# TMS320F28335_DSP.net
KiCad netlist of a schematic drawn in Altium Designer
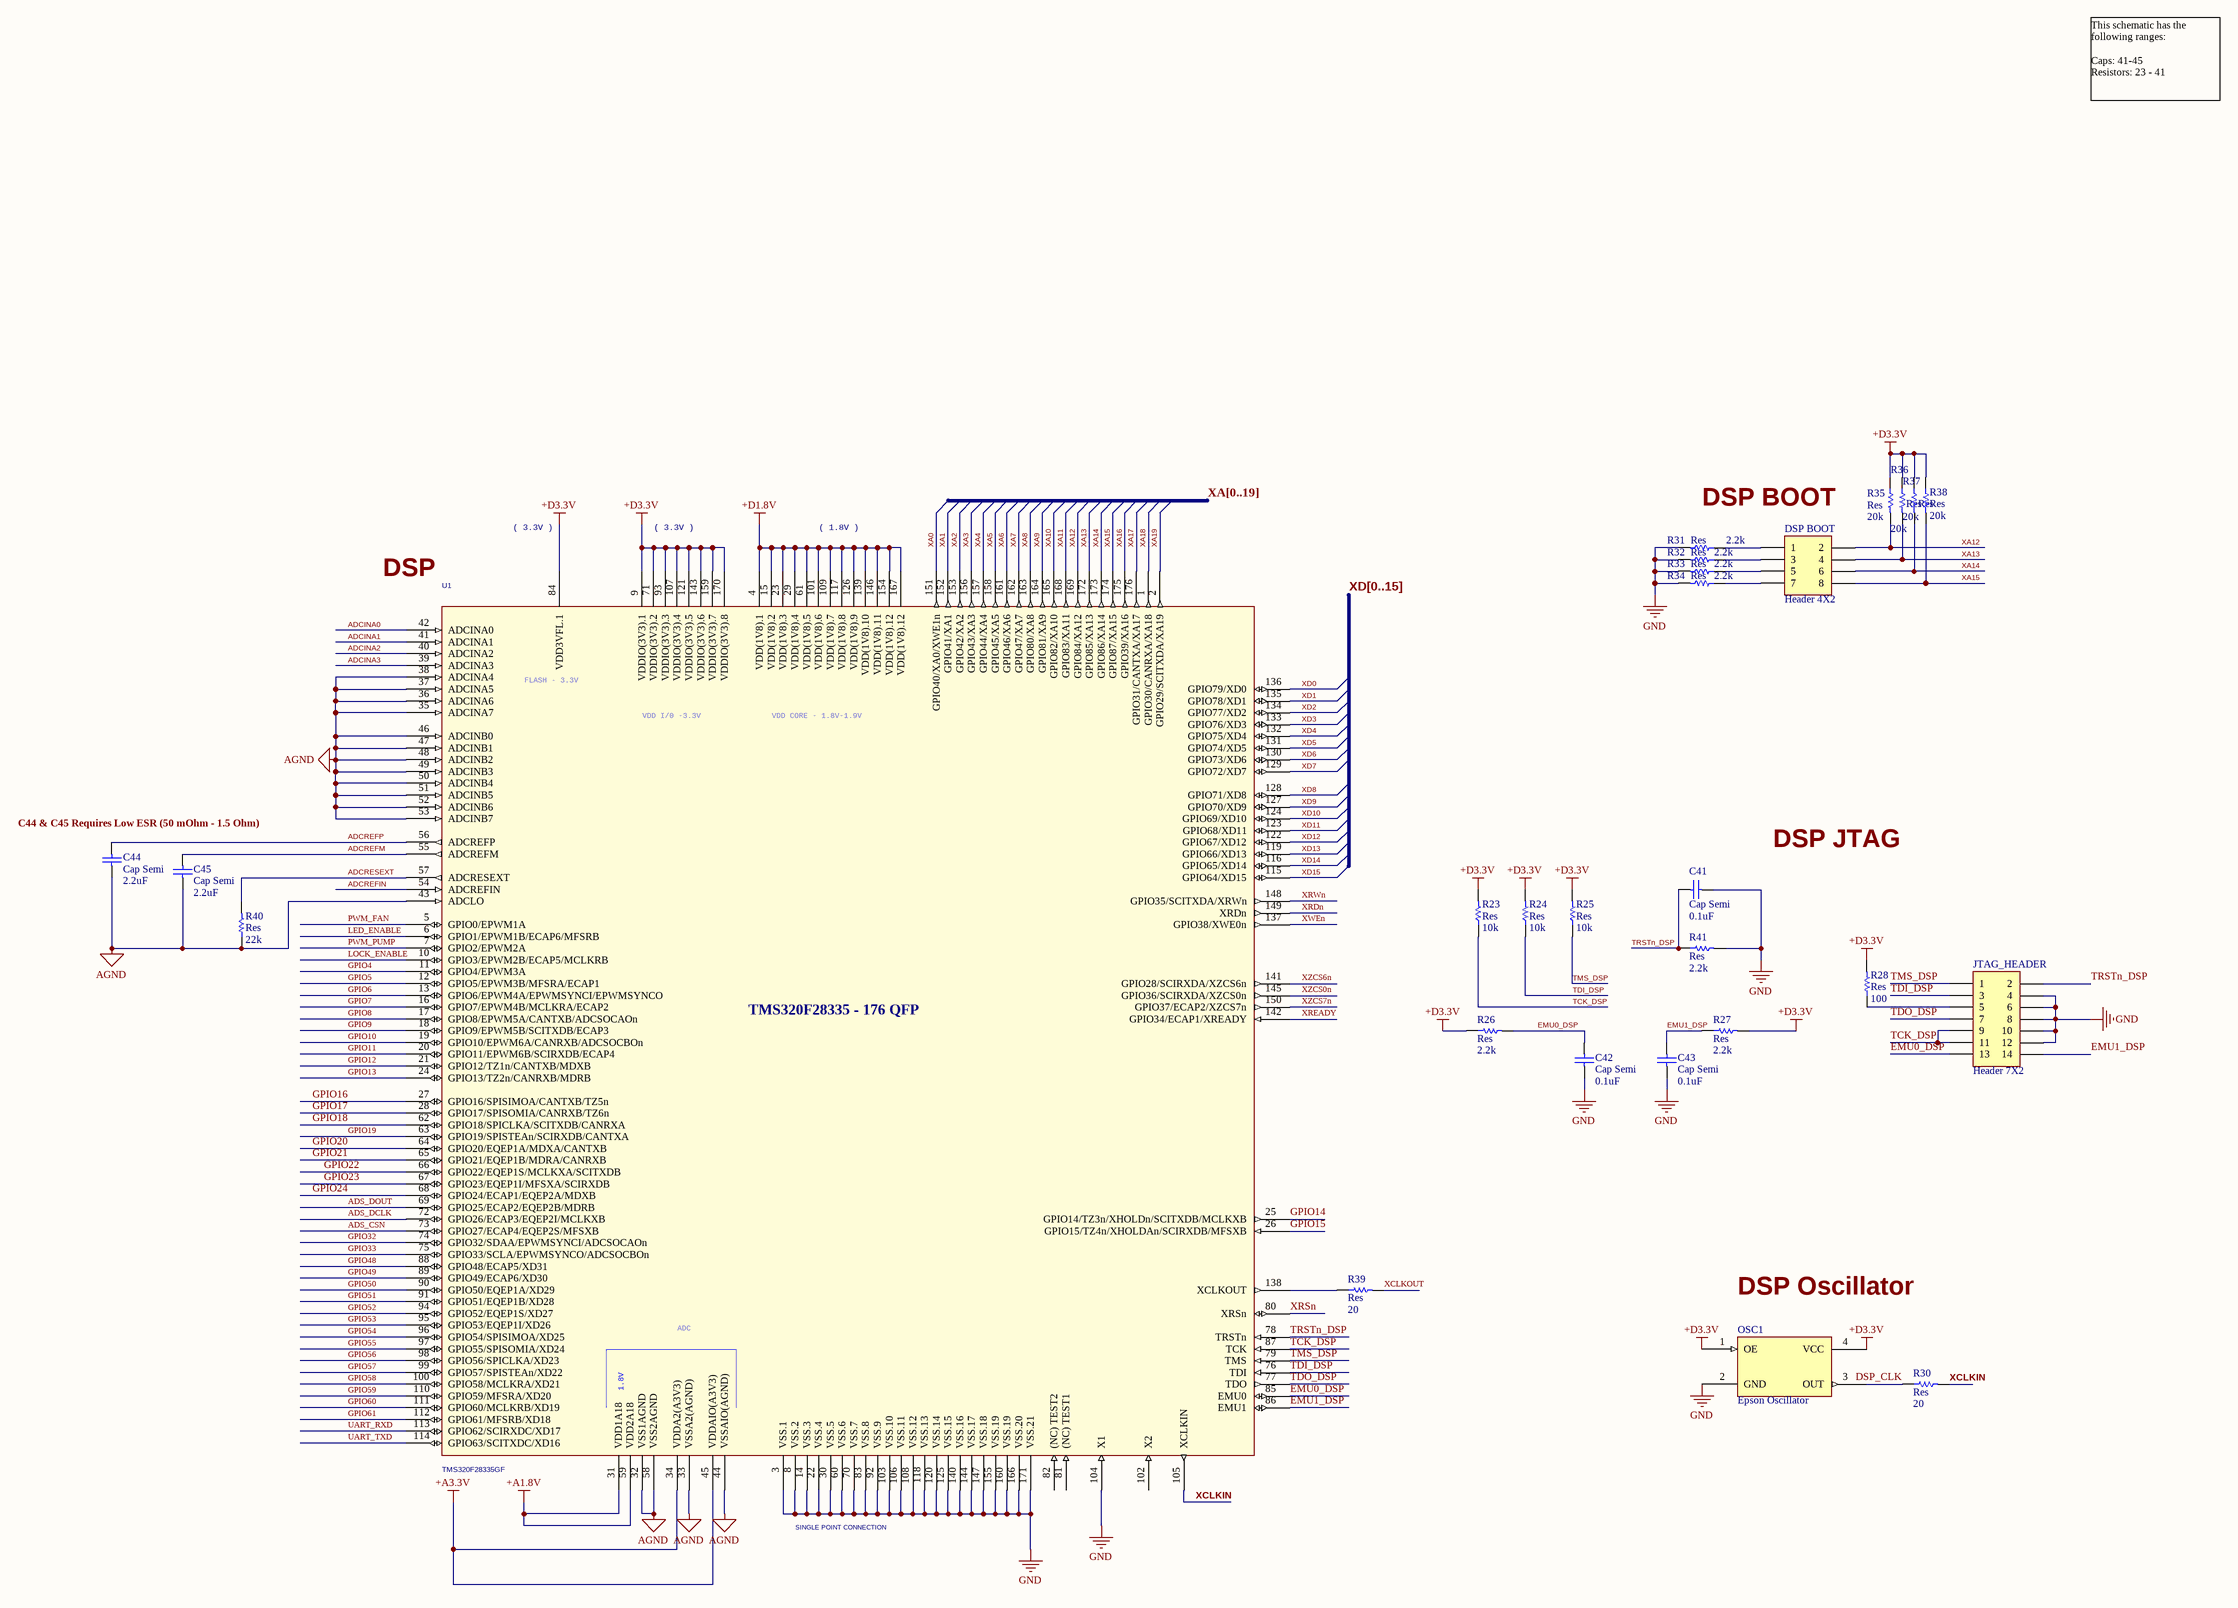
[diagram p0: TMS320F28335_DSP.SchDoc]

(export (version "E")
  (design (tool "Eeschema 10.0.6"))
  (components
    (comp (ref "C41")
      (value "Cap Semi")
      (footprint "0805")
      (description "Capacitor (Semiconductor SIM Model)")
      (fields (field (name "ALTIUM_VALUE") "0.1uF") (field (name "PUBLISHER") "Altium Limited"))
      (libsource (lib "Miscellaneous Devices") (part "Cap Semi"))
    )
    (comp (ref "C42")
      (value "Cap Semi")
      (footprint "0805")
      (description "Capacitor (Semiconductor SIM Model)")
      (fields (field (name "ALTIUM_VALUE") "0.1uF") (field (name "PUBLISHER") "Altium Limited"))
      (libsource (lib "Miscellaneous Devices") (part "Cap Semi"))
    )
    (comp (ref "C43")
      (value "Cap Semi")
      (footprint "0805")
      (description "Capacitor (Semiconductor SIM Model)")
      (fields (field (name "ALTIUM_VALUE") "0.1uF") (field (name "PUBLISHER") "Altium Limited"))
      (libsource (lib "Miscellaneous Devices") (part "Cap Semi"))
    )
    (comp (ref "C44")
      (value "Cap Semi")
      (footprint "0805")
      (description "Capacitor (Semiconductor SIM Model)")
      (fields (field (name "ALTIUM_VALUE") "2.2uF") (field (name "PUBLISHER") "Altium Limited"))
      (libsource (lib "Miscellaneous Devices") (part "Cap Semi"))
    )
    (comp (ref "C45")
      (value "Cap Semi")
      (footprint "0805")
      (description "Capacitor (Semiconductor SIM Model)")
      (fields (field (name "ALTIUM_VALUE") "2.2uF") (field (name "PUBLISHER") "Altium Limited"))
      (libsource (lib "Miscellaneous Devices") (part "Cap Semi"))
    )
    (comp (ref "DSP BOOT")
      (value "Header 4X2")
      (footprint "HDR2X4")
      (description "Header, 4-Pin, Dual row")
      (fields (field (name "PUBLISHER") "Altium Limited"))
      (libsource (lib "Miscellaneous Connectors") (part "Header 4X2"))
    )
    (comp (ref "JTAG_HEADER")
      (value "Header 7X2")
      (footprint "HDR2X7")
      (description "Header, 7-Pin, Dual row")
      (fields (field (name "PUBLISHER") "Altium Limited"))
      (libsource (lib "Miscellaneous Connectors") (part "Header 7X2"))
    )
    (comp (ref "OSC1")
      (value "Epson Oscillator")
      (footprint "Oscillator")
      (description "15Mhz Epson Clock")
      (libsource (lib "F28335_DSC_Breakout") (part "Oscillator"))
    )
    (comp (ref "R23")
      (value "Res")
      (footprint "0805")
      (description "Semiconductor Resistor")
      (fields (field (name "ALTIUM_VALUE") "10k") (field (name "PUBLISHER") "Altium Limited"))
      (libsource (lib "F28335_DSC_Breakout") (part "Res Semi"))
    )
    (comp (ref "R24")
      (value "Res")
      (footprint "0805")
      (description "Semiconductor Resistor")
      (fields (field (name "ALTIUM_VALUE") "10k") (field (name "PUBLISHER") "Altium Limited"))
      (libsource (lib "F28335_DSC_Breakout") (part "Res Semi"))
    )
    (comp (ref "R25")
      (value "Res")
      (footprint "0805")
      (description "Semiconductor Resistor")
      (fields (field (name "ALTIUM_VALUE") "10k") (field (name "PUBLISHER") "Altium Limited"))
      (libsource (lib "F28335_DSC_Breakout") (part "Res Semi"))
    )
    (comp (ref "R26")
      (value "Res")
      (footprint "0805")
      (description "Semiconductor Resistor")
      (fields (field (name "ALTIUM_VALUE") "2.2k") (field (name "PUBLISHER") "Altium Limited"))
      (libsource (lib "F28335_DSC_Breakout") (part "Res Semi"))
    )
    (comp (ref "R27")
      (value "Res")
      (footprint "0805")
      (description "Semiconductor Resistor")
      (fields (field (name "ALTIUM_VALUE") "2.2k") (field (name "PUBLISHER") "Altium Limited"))
      (libsource (lib "F28335_DSC_Breakout") (part "Res Semi"))
    )
    (comp (ref "R28")
      (value "Res")
      (footprint "0805")
      (description "Semiconductor Resistor")
      (fields (field (name "ALTIUM_VALUE") "100") (field (name "PUBLISHER") "Altium Limited"))
      (libsource (lib "F28335_DSC_Breakout") (part "Res Semi"))
    )
    (comp (ref "R30")
      (value "Res")
      (footprint "0805")
      (description "Semiconductor Resistor")
      (fields (field (name "ALTIUM_VALUE") "20") (field (name "PUBLISHER") "Altium Limited"))
      (libsource (lib "F28335_DSC_Breakout") (part "Res Semi"))
    )
    (comp (ref "R31")
      (value "Res")
      (footprint "0805")
      (description "Semiconductor Resistor")
      (fields (field (name "ALTIUM_VALUE") "2.2k") (field (name "PUBLISHER") "Altium Limited"))
      (libsource (lib "F28335_DSC_Breakout") (part "Res Semi"))
    )
    (comp (ref "R32")
      (value "Res")
      (footprint "0805")
      (description "Semiconductor Resistor")
      (fields (field (name "ALTIUM_VALUE") "2.2k") (field (name "PUBLISHER") "Altium Limited"))
      (libsource (lib "F28335_DSC_Breakout") (part "Res Semi"))
    )
    (comp (ref "R33")
      (value "Res")
      (footprint "0805")
      (description "Semiconductor Resistor")
      (fields (field (name "ALTIUM_VALUE") "2.2k") (field (name "PUBLISHER") "Altium Limited"))
      (libsource (lib "F28335_DSC_Breakout") (part "Res Semi"))
    )
    (comp (ref "R34")
      (value "Res")
      (footprint "0805")
      (description "Semiconductor Resistor")
      (fields (field (name "ALTIUM_VALUE") "2.2k") (field (name "PUBLISHER") "Altium Limited"))
      (libsource (lib "F28335_DSC_Breakout") (part "Res Semi"))
    )
    (comp (ref "R35")
      (value "Res")
      (footprint "0805")
      (description "Semiconductor Resistor")
      (fields (field (name "ALTIUM_VALUE") "20k") (field (name "PUBLISHER") "Altium Limited"))
      (libsource (lib "F28335_DSC_Breakout") (part "Res Semi"))
    )
    (comp (ref "R36")
      (value "Res")
      (footprint "0805")
      (description "Semiconductor Resistor")
      (fields (field (name "ALTIUM_VALUE") "20k") (field (name "PUBLISHER") "Altium Limited"))
      (libsource (lib "F28335_DSC_Breakout") (part "Res Semi"))
    )
    (comp (ref "R37")
      (value "Res")
      (footprint "0805")
      (description "Semiconductor Resistor")
      (fields (field (name "ALTIUM_VALUE") "20k") (field (name "PUBLISHER") "Altium Limited"))
      (libsource (lib "F28335_DSC_Breakout") (part "Res Semi"))
    )
    (comp (ref "R38")
      (value "Res")
      (footprint "0805")
      (description "Semiconductor Resistor")
      (fields (field (name "ALTIUM_VALUE") "20k") (field (name "PUBLISHER") "Altium Limited"))
      (libsource (lib "F28335_DSC_Breakout") (part "Res Semi"))
    )
    (comp (ref "R39")
      (value "Res")
      (footprint "0805")
      (description "Semiconductor Resistor")
      (fields (field (name "ALTIUM_VALUE") "20") (field (name "PUBLISHER") "Altium Limited"))
      (libsource (lib "F28335_DSC_Breakout") (part "Res Semi"))
    )
    (comp (ref "R40")
      (value "Res")
      (footprint "0805")
      (description "Semiconductor Resistor")
      (fields (field (name "ALTIUM_VALUE") "22k") (field (name "PUBLISHER") "Altium Limited"))
      (libsource (lib "F28335_DSC_Breakout") (part "Res Semi"))
    )
    (comp (ref "R41")
      (value "Res")
      (footprint "0805")
      (description "Semiconductor Resistor")
      (fields (field (name "ALTIUM_VALUE") "2.2k") (field (name "PUBLISHER") "Altium Limited"))
      (libsource (lib "F28335_DSC_Breakout") (part "Res Semi"))
    )
    (comp (ref "U1")
      (value "TMS320F28335GF")
      (footprint "QFP176")
      (description "Texas Instruments F28335")
      (libsource (lib "addl") (part "TMS320F283XXPGF_23"))
    )
  )
  (nets
    (net (code "1") (name "+A1.8V") (class "Default")
      (node (ref "U1") (pin "31") (pinfunction "VDD1A18_31") (pintype "power_in"))
      (node (ref "U1") (pin "59") (pinfunction "VDD2A18_59") (pintype "power_in"))
    )
    (net (code "2") (name "+A3.3V") (class "Default")
      (node (ref "U1") (pin "34") (pinfunction "VDDA2(A3V3)_34") (pintype "power_in"))
      (node (ref "U1") (pin "45") (pinfunction "VDDAIO(A3V3)_45") (pintype "power_in"))
    )
    (net (code "3") (name "+D1.8V") (class "Default")
      (node (ref "U1") (pin "101") (pinfunction "VDD(1V8).6_101") (pintype "power_in"))
      (node (ref "U1") (pin "109") (pinfunction "VDD(1V8).7_109") (pintype "power_in"))
      (node (ref "U1") (pin "117") (pinfunction "VDD(1V8).8_117") (pintype "power_in"))
      (node (ref "U1") (pin "126") (pinfunction "VDD(1V8).9_126") (pintype "power_in"))
      (node (ref "U1") (pin "139") (pinfunction "VDD(1V8).10_139") (pintype "power_in"))
      (node (ref "U1") (pin "146") (pinfunction "VDD(1V8).11_146") (pintype "power_in"))
      (node (ref "U1") (pin "15") (pinfunction "VDD(1V8).2_15") (pintype "power_in"))
      (node (ref "U1") (pin "154") (pinfunction "VDD(1V8).12_154") (pintype "power_in"))
      (node (ref "U1") (pin "167") (pinfunction "VDD(1V8).12_167") (pintype "power_in"))
      (node (ref "U1") (pin "23") (pinfunction "VDD(1V8).3_23") (pintype "power_in"))
      (node (ref "U1") (pin "29") (pinfunction "VDD(1V8).4_29") (pintype "power_in"))
      (node (ref "U1") (pin "4") (pinfunction "VDD(1V8).1_4") (pintype "power_in"))
      (node (ref "U1") (pin "61") (pinfunction "VDD(1V8).5_61") (pintype "power_in"))
    )
    (net (code "4") (name "+D3.3V") (class "Default")
      (node (ref "OSC1") (pin "1") (pinfunction "OE_1") (pintype "input"))
      (node (ref "OSC1") (pin "4") (pinfunction "VCC_4") (pintype "power_in"))
      (node (ref "R23") (pin "2") (pinfunction "2_2") (pintype "passive"))
      (node (ref "R24") (pin "2") (pinfunction "2_2") (pintype "passive"))
      (node (ref "R25") (pin "2") (pinfunction "2_2") (pintype "passive"))
      (node (ref "R26") (pin "1") (pinfunction "1_1") (pintype "passive"))
      (node (ref "R27") (pin "2") (pinfunction "2_2") (pintype "passive"))
      (node (ref "R28") (pin "2") (pinfunction "2_2") (pintype "passive"))
      (node (ref "R35") (pin "1") (pinfunction "1_1") (pintype "passive"))
      (node (ref "R36") (pin "1") (pinfunction "1_1") (pintype "passive"))
      (node (ref "R37") (pin "1") (pinfunction "1_1") (pintype "passive"))
      (node (ref "R38") (pin "1") (pinfunction "1_1") (pintype "passive"))
      (node (ref "U1") (pin "107") (pinfunction "VDDIO(3V3).4_107") (pintype "power_in"))
      (node (ref "U1") (pin "121") (pinfunction "VDDIO(3V3).5_121") (pintype "power_in"))
      (node (ref "U1") (pin "143") (pinfunction "VDDIO(3V3).6_143") (pintype "power_in"))
      (node (ref "U1") (pin "159") (pinfunction "VDDIO(3V3).7_159") (pintype "power_in"))
      (node (ref "U1") (pin "170") (pinfunction "VDDIO(3V3).8_170") (pintype "power_in"))
      (node (ref "U1") (pin "71") (pinfunction "VDDIO(3V3).2_71") (pintype "power_in"))
      (node (ref "U1") (pin "84") (pinfunction "VDD3VFL.1_84") (pintype "power_in"))
      (node (ref "U1") (pin "9") (pinfunction "VDDIO(3V3).1_9") (pintype "power_in"))
      (node (ref "U1") (pin "93") (pinfunction "VDDIO(3V3).3_93") (pintype "power_in"))
    )
    (net (code "5") (name "/ADCINA0") (class "Default")
      (node (ref "U1") (pin "42") (pinfunction "ADCINA0_42") (pintype "input"))
    )
    (net (code "6") (name "/ADCINA1") (class "Default")
      (node (ref "U1") (pin "41") (pinfunction "ADCINA1_41") (pintype "input"))
    )
    (net (code "7") (name "/ADCINA2") (class "Default")
      (node (ref "U1") (pin "40") (pinfunction "ADCINA2_40") (pintype "input"))
    )
    (net (code "8") (name "/ADCINA3") (class "Default")
      (node (ref "U1") (pin "39") (pinfunction "ADCINA3_39") (pintype "input"))
    )
    (net (code "9") (name "/ADCREFIN") (class "Default")
      (node (ref "U1") (pin "54") (pinfunction "ADCREFIN_54") (pintype "input"))
    )
    (net (code "10") (name "/ADCREFM") (class "Default")
      (node (ref "C45") (pin "1") (pinfunction "1_1") (pintype "passive"))
      (node (ref "U1") (pin "55") (pinfunction "ADCREFM_55") (pintype "output"))
    )
    (net (code "11") (name "/ADCREFP") (class "Default")
      (node (ref "C44") (pin "1") (pinfunction "1_1") (pintype "passive"))
      (node (ref "U1") (pin "56") (pinfunction "ADCREFP_56") (pintype "output"))
    )
    (net (code "12") (name "/ADCRESEXT") (class "Default")
      (node (ref "R40") (pin "2") (pinfunction "2_2") (pintype "passive"))
      (node (ref "U1") (pin "57") (pinfunction "ADCRESEXT_57") (pintype "output"))
    )
    (net (code "13") (name "/ADS_CSN") (class "Default")
      (node (ref "U1") (pin "73") (pinfunction "GPIO27/ECAP4/EQEP2S/MFSXB_73") (pintype "bidirectional"))
    )
    (net (code "14") (name "/ADS_DCLK") (class "Default")
      (node (ref "U1") (pin "72") (pinfunction "GPIO26/ECAP3/EQEP2I/MCLKXB_72") (pintype "bidirectional"))
    )
    (net (code "15") (name "/ADS_DOUT") (class "Default")
      (node (ref "U1") (pin "69") (pinfunction "GPIO25/ECAP2/EQEP2B/MDRB_69") (pintype "bidirectional"))
    )
    (net (code "17") (name "/EMU0_DSP") (class "Default")
      (node (ref "C42") (pin "2") (pinfunction "2_2") (pintype "passive"))
      (node (ref "JTAG_HEADER") (pin "13") (pinfunction "13_13") (pintype "passive"))
      (node (ref "R26") (pin "2") (pinfunction "2_2") (pintype "passive"))
      (node (ref "U1") (pin "85") (pinfunction "EMU0_85") (pintype "bidirectional"))
    )
    (net (code "18") (name "/EMU1_DSP") (class "Default")
      (node (ref "C43") (pin "2") (pinfunction "2_2") (pintype "passive"))
      (node (ref "JTAG_HEADER") (pin "14") (pinfunction "14_14") (pintype "passive"))
      (node (ref "R27") (pin "1") (pinfunction "1_1") (pintype "passive"))
      (node (ref "U1") (pin "86") (pinfunction "EMU1_86") (pintype "bidirectional"))
    )
    (net (code "19") (name "/GPIO4") (class "Default")
      (node (ref "U1") (pin "11") (pinfunction "GPIO4/EPWM3A_11") (pintype "bidirectional"))
    )
    (net (code "20") (name "/GPIO5") (class "Default")
      (node (ref "U1") (pin "12") (pinfunction "GPIO5/EPWM3B/MFSRA/ECAP1_12") (pintype "bidirectional"))
    )
    (net (code "21") (name "/GPIO6") (class "Default")
      (node (ref "U1") (pin "13") (pinfunction "GPIO6/EPWM4A/EPWMSYNCI/EPWMSYNCO_13") (pintype "bidirectional"))
    )
    (net (code "22") (name "/GPIO7") (class "Default")
      (node (ref "U1") (pin "16") (pinfunction "GPIO7/EPWM4B/MCLKRA/ECAP2_16") (pintype "bidirectional"))
    )
    (net (code "23") (name "/GPIO8") (class "Default")
      (node (ref "U1") (pin "17") (pinfunction "GPIO8/EPWM5A/CANTXB/ADCSOCAOn_17") (pintype "bidirectional"))
    )
    (net (code "24") (name "/GPIO9") (class "Default")
      (node (ref "U1") (pin "18") (pinfunction "GPIO9/EPWM5B/SCITXDB/ECAP3_18") (pintype "bidirectional"))
    )
    (net (code "25") (name "/GPIO10") (class "Default")
      (node (ref "U1") (pin "19") (pinfunction "GPIO10/EPWM6A/CANRXB/ADCSOCBOn_19") (pintype "bidirectional"))
    )
    (net (code "26") (name "/GPIO11") (class "Default")
      (node (ref "U1") (pin "20") (pinfunction "GPIO11/EPWM6B/SCIRXDB/ECAP4_20") (pintype "bidirectional"))
    )
    (net (code "27") (name "/GPIO12") (class "Default")
      (node (ref "U1") (pin "21") (pinfunction "GPIO12/TZ1n/CANTXB/MDXB_21") (pintype "bidirectional"))
    )
    (net (code "28") (name "/GPIO13") (class "Default")
      (node (ref "U1") (pin "24") (pinfunction "GPIO13/TZ2n/CANRXB/MDRB_24") (pintype "bidirectional"))
    )
    (net (code "29") (name "/GPIO14") (class "Default")
      (node (ref "U1") (pin "25") (pinfunction "GPIO14/TZ3n/XHOLDn/SCITXDB/MCLKXB_25") (pintype "output"))
    )
    (net (code "30") (name "/GPIO15") (class "Default")
      (node (ref "U1") (pin "26") (pinfunction "GPIO15/TZ4n/XHOLDAn/SCIRXDB/MFSXB_26") (pintype "input"))
    )
    (net (code "31") (name "/GPIO16") (class "Default")
      (node (ref "U1") (pin "27") (pinfunction "GPIO16/SPISIMOA/CANTXB/TZ5n_27") (pintype "bidirectional"))
    )
    (net (code "32") (name "/GPIO17") (class "Default")
      (node (ref "U1") (pin "28") (pinfunction "GPIO17/SPISOMIA/CANRXB/TZ6n_28") (pintype "bidirectional"))
    )
    (net (code "33") (name "/GPIO18") (class "Default")
      (node (ref "U1") (pin "62") (pinfunction "GPIO18/SPICLKA/SCITXDB/CANRXA_62") (pintype "bidirectional"))
    )
    (net (code "34") (name "/GPIO19") (class "Default")
      (node (ref "U1") (pin "63") (pinfunction "GPIO19/SPISTEAn/SCIRXDB/CANTXA_63") (pintype "bidirectional"))
    )
    (net (code "35") (name "/GPIO20") (class "Default")
      (node (ref "U1") (pin "64") (pinfunction "GPIO20/EQEP1A/MDXA/CANTXB_64") (pintype "bidirectional"))
    )
    (net (code "36") (name "/GPIO21") (class "Default")
      (node (ref "U1") (pin "65") (pinfunction "GPIO21/EQEP1B/MDRA/CANRXB_65") (pintype "bidirectional"))
    )
    (net (code "37") (name "/GPIO22") (class "Default")
      (node (ref "U1") (pin "66") (pinfunction "GPIO22/EQEP1S/MCLKXA/SCITXDB_66") (pintype "bidirectional"))
    )
    (net (code "38") (name "/GPIO23") (class "Default")
      (node (ref "U1") (pin "67") (pinfunction "GPIO23/EQEP1I/MFSXA/SCIRXDB_67") (pintype "bidirectional"))
    )
    (net (code "39") (name "/GPIO24") (class "Default")
      (node (ref "U1") (pin "68") (pinfunction "GPIO24/ECAP1/EQEP2A/MDXB_68") (pintype "bidirectional"))
    )
    (net (code "40") (name "/GPIO32") (class "Default")
      (node (ref "U1") (pin "74") (pinfunction "GPIO32/SDAA/EPWMSYNCI/ADCSOCAOn_74") (pintype "bidirectional"))
    )
    (net (code "41") (name "/GPIO33") (class "Default")
      (node (ref "U1") (pin "75") (pinfunction "GPIO33/SCLA/EPWMSYNCO/ADCSOCBOn_75") (pintype "bidirectional"))
    )
    (net (code "42") (name "/GPIO48") (class "Default")
      (node (ref "U1") (pin "88") (pinfunction "GPIO48/ECAP5/XD31_88") (pintype "bidirectional"))
    )
    (net (code "43") (name "/GPIO49") (class "Default")
      (node (ref "U1") (pin "89") (pinfunction "GPIO49/ECAP6/XD30_89") (pintype "bidirectional"))
    )
    (net (code "44") (name "/GPIO50") (class "Default")
      (node (ref "U1") (pin "90") (pinfunction "GPIO50/EQEP1A/XD29_90") (pintype "bidirectional"))
    )
    (net (code "45") (name "/GPIO51") (class "Default")
      (node (ref "U1") (pin "91") (pinfunction "GPIO51/EQEP1B/XD28_91") (pintype "bidirectional"))
    )
    (net (code "46") (name "/GPIO52") (class "Default")
      (node (ref "U1") (pin "94") (pinfunction "GPIO52/EQEP1S/XD27_94") (pintype "bidirectional"))
    )
    (net (code "47") (name "/GPIO53") (class "Default")
      (node (ref "U1") (pin "95") (pinfunction "GPIO53/EQEP1I/XD26_95") (pintype "bidirectional"))
    )
    (net (code "48") (name "/GPIO54") (class "Default")
      (node (ref "U1") (pin "96") (pinfunction "GPIO54/SPISIMOA/XD25_96") (pintype "bidirectional"))
    )
    (net (code "49") (name "/GPIO55") (class "Default")
      (node (ref "U1") (pin "97") (pinfunction "GPIO55/SPISOMIA/XD24_97") (pintype "bidirectional"))
    )
    (net (code "50") (name "/GPIO56") (class "Default")
      (node (ref "U1") (pin "98") (pinfunction "GPIO56/SPICLKA/XD23_98") (pintype "bidirectional"))
    )
    (net (code "51") (name "/GPIO57") (class "Default")
      (node (ref "U1") (pin "99") (pinfunction "GPIO57/SPISTEAn/XD22_99") (pintype "bidirectional"))
    )
    (net (code "52") (name "/GPIO58") (class "Default")
      (node (ref "U1") (pin "100") (pinfunction "GPIO58/MCLKRA/XD21_100") (pintype "bidirectional"))
    )
    (net (code "53") (name "/GPIO59") (class "Default")
      (node (ref "U1") (pin "110") (pinfunction "GPIO59/MFSRA/XD20_110") (pintype "bidirectional"))
    )
    (net (code "54") (name "/GPIO60") (class "Default")
      (node (ref "U1") (pin "111") (pinfunction "GPIO60/MCLKRB/XD19_111") (pintype "bidirectional"))
    )
    (net (code "55") (name "/GPIO61") (class "Default")
      (node (ref "U1") (pin "112") (pinfunction "GPIO61/MFSRB/XD18_112") (pintype "bidirectional"))
    )
    (net (code "56") (name "/LED_ENABLE") (class "Default")
      (node (ref "U1") (pin "6") (pinfunction "GPIO1/EPWM1B/ECAP6/MFSRB_6") (pintype "bidirectional"))
    )
    (net (code "57") (name "/LOCK_ENABLE") (class "Default")
      (node (ref "U1") (pin "10") (pinfunction "GPIO3/EPWM2B/ECAP5/MCLKRB_10") (pintype "bidirectional"))
    )
    (net (code "58") (name "/PWM_FAN") (class "Default")
      (node (ref "U1") (pin "5") (pinfunction "GPIO0/EPWM1A_5") (pintype "bidirectional"))
    )
    (net (code "59") (name "/PWM_PUMP") (class "Default")
      (node (ref "U1") (pin "7") (pinfunction "GPIO2/EPWM2A_7") (pintype "bidirectional"))
    )
    (net (code "60") (name "/TCK_DSP") (class "Default")
      (node (ref "JTAG_HEADER") (pin "11") (pinfunction "11_11") (pintype "passive"))
      (node (ref "JTAG_HEADER") (pin "9") (pinfunction "9_9") (pintype "passive"))
      (node (ref "R23") (pin "1") (pinfunction "1_1") (pintype "passive"))
      (node (ref "U1") (pin "87") (pinfunction "TCK_87") (pintype "input"))
    )
    (net (code "61") (name "/TDI_DSP") (class "Default")
      (node (ref "JTAG_HEADER") (pin "3") (pinfunction "3_3") (pintype "passive"))
      (node (ref "R24") (pin "1") (pinfunction "1_1") (pintype "passive"))
      (node (ref "U1") (pin "76") (pinfunction "TDI_76") (pintype "input"))
    )
    (net (code "62") (name "/TDO_DSP") (class "Default")
      (node (ref "JTAG_HEADER") (pin "7") (pinfunction "7_7") (pintype "passive"))
      (node (ref "U1") (pin "77") (pinfunction "TDO_77") (pintype "output"))
    )
    (net (code "63") (name "/TMS_DSP") (class "Default")
      (node (ref "JTAG_HEADER") (pin "1") (pinfunction "1_1") (pintype "passive"))
      (node (ref "R25") (pin "1") (pinfunction "1_1") (pintype "passive"))
      (node (ref "U1") (pin "79") (pinfunction "TMS_79") (pintype "input"))
    )
    (net (code "64") (name "/TRSTn_DSP") (class "Default")
      (node (ref "C41") (pin "2") (pinfunction "2_2") (pintype "passive"))
      (node (ref "JTAG_HEADER") (pin "2") (pinfunction "2_2") (pintype "passive"))
      (node (ref "R41") (pin "1") (pinfunction "1_1") (pintype "passive"))
      (node (ref "U1") (pin "78") (pinfunction "TRSTn_78") (pintype "input"))
    )
    (net (code "65") (name "/UART_RXD") (class "Default")
      (node (ref "U1") (pin "113") (pinfunction "GPIO62/SCIRXDC/XD17_113") (pintype "bidirectional"))
    )
    (net (code "66") (name "/UART_TXD") (class "Default")
      (node (ref "U1") (pin "114") (pinfunction "GPIO63/SCITXDC/XD16_114") (pintype "bidirectional"))
    )
    (net (code "67") (name "/XA0") (class "Default")
      (node (ref "U1") (pin "151") (pinfunction "GPIO40/XA0/XWE1n_151") (pintype "output"))
    )
    (net (code "68") (name "/XA1") (class "Default")
      (node (ref "U1") (pin "152") (pinfunction "GPIO41/XA1_152") (pintype "output"))
    )
    (net (code "69") (name "/XA2") (class "Default")
      (node (ref "U1") (pin "153") (pinfunction "GPIO42/XA2_153") (pintype "output"))
    )
    (net (code "70") (name "/XA3") (class "Default")
      (node (ref "U1") (pin "156") (pinfunction "GPIO43/XA3_156") (pintype "output"))
    )
    (net (code "71") (name "/XA4") (class "Default")
      (node (ref "U1") (pin "157") (pinfunction "GPIO44/XA4_157") (pintype "output"))
    )
    (net (code "72") (name "/XA5") (class "Default")
      (node (ref "U1") (pin "158") (pinfunction "GPIO45/XA5_158") (pintype "output"))
    )
    (net (code "73") (name "/XA6") (class "Default")
      (node (ref "U1") (pin "161") (pinfunction "GPIO46/XA6_161") (pintype "output"))
    )
    (net (code "74") (name "/XA7") (class "Default")
      (node (ref "U1") (pin "162") (pinfunction "GPIO47/XA7_162") (pintype "output"))
    )
    (net (code "75") (name "/XA8") (class "Default")
      (node (ref "U1") (pin "163") (pinfunction "GPIO80/XA8_163") (pintype "output"))
    )
    (net (code "76") (name "/XA9") (class "Default")
      (node (ref "U1") (pin "164") (pinfunction "GPIO81/XA9_164") (pintype "output"))
    )
    (net (code "77") (name "/XA10") (class "Default")
      (node (ref "U1") (pin "165") (pinfunction "GPIO82/XA10_165") (pintype "output"))
    )
    (net (code "78") (name "/XA11") (class "Default")
      (node (ref "U1") (pin "168") (pinfunction "GPIO83/XA11_168") (pintype "output"))
    )
    (net (code "79") (name "/XA12") (class "Default")
      (node (ref "DSP BOOT") (pin "2") (pinfunction "2_2") (pintype "passive"))
      (node (ref "R35") (pin "2") (pinfunction "2_2") (pintype "passive"))
      (node (ref "U1") (pin "169") (pinfunction "GPIO84/XA12_169") (pintype "output"))
    )
    (net (code "80") (name "/XA13") (class "Default")
      (node (ref "DSP BOOT") (pin "4") (pinfunction "4_4") (pintype "passive"))
      (node (ref "R36") (pin "2") (pinfunction "2_2") (pintype "passive"))
      (node (ref "U1") (pin "172") (pinfunction "GPIO85/XA13_172") (pintype "output"))
    )
    (net (code "81") (name "/XA14") (class "Default")
      (node (ref "DSP BOOT") (pin "6") (pinfunction "6_6") (pintype "passive"))
      (node (ref "R37") (pin "2") (pinfunction "2_2") (pintype "passive"))
      (node (ref "U1") (pin "173") (pinfunction "GPIO86/XA14_173") (pintype "output"))
    )
    (net (code "82") (name "/XA15") (class "Default")
      (node (ref "DSP BOOT") (pin "8") (pinfunction "8_8") (pintype "passive"))
      (node (ref "R38") (pin "2") (pinfunction "2_2") (pintype "passive"))
      (node (ref "U1") (pin "174") (pinfunction "GPIO87/XA15_174") (pintype "output"))
    )
    (net (code "83") (name "/XA16") (class "Default")
      (node (ref "U1") (pin "175") (pinfunction "GPIO39/XA16_175") (pintype "output"))
    )
    (net (code "84") (name "/XA17") (class "Default")
      (node (ref "U1") (pin "176") (pinfunction "GPIO31/CANTXA/XA17_176") (pintype "output"))
    )
    (net (code "85") (name "/XA18") (class "Default")
      (node (ref "U1") (pin "1") (pinfunction "GPIO30/CANRXA/XA18_1") (pintype "output"))
    )
    (net (code "86") (name "/XA19") (class "Default")
      (node (ref "U1") (pin "2") (pinfunction "GPIO29/SCITXDA/XA19_2") (pintype "output"))
    )
    (net (code "88") (name "/XCLKIN") (class "Default")
      (node (ref "R30") (pin "2") (pinfunction "2_2") (pintype "passive"))
      (node (ref "U1") (pin "105") (pinfunction "XCLKIN_105") (pintype "output"))
    )
    (net (code "89") (name "/XCLKOUT") (class "Default")
      (node (ref "R39") (pin "2") (pinfunction "2_2") (pintype "passive"))
    )
    (net (code "90") (name "/XD0") (class "Default")
      (node (ref "U1") (pin "136") (pinfunction "GPIO79/XD0_136") (pintype "bidirectional"))
    )
    (net (code "91") (name "/XD1") (class "Default")
      (node (ref "U1") (pin "135") (pinfunction "GPIO78/XD1_135") (pintype "bidirectional"))
    )
    (net (code "92") (name "/XD2") (class "Default")
      (node (ref "U1") (pin "134") (pinfunction "GPIO77/XD2_134") (pintype "bidirectional"))
    )
    (net (code "93") (name "/XD3") (class "Default")
      (node (ref "U1") (pin "133") (pinfunction "GPIO76/XD3_133") (pintype "bidirectional"))
    )
    (net (code "94") (name "/XD4") (class "Default")
      (node (ref "U1") (pin "132") (pinfunction "GPIO75/XD4_132") (pintype "bidirectional"))
    )
    (net (code "95") (name "/XD5") (class "Default")
      (node (ref "U1") (pin "131") (pinfunction "GPIO74/XD5_131") (pintype "bidirectional"))
    )
    (net (code "96") (name "/XD6") (class "Default")
      (node (ref "U1") (pin "130") (pinfunction "GPIO73/XD6_130") (pintype "bidirectional"))
    )
    (net (code "97") (name "/XD7") (class "Default")
      (node (ref "U1") (pin "129") (pinfunction "GPIO72/XD7_129") (pintype "bidirectional"))
    )
    (net (code "98") (name "/XD8") (class "Default")
      (node (ref "U1") (pin "128") (pinfunction "GPIO71/XD8_128") (pintype "bidirectional"))
    )
    (net (code "99") (name "/XD9") (class "Default")
      (node (ref "U1") (pin "127") (pinfunction "GPIO70/XD9_127") (pintype "bidirectional"))
    )
    (net (code "100") (name "/XD10") (class "Default")
      (node (ref "U1") (pin "124") (pinfunction "GPIO69/XD10_124") (pintype "bidirectional"))
    )
    (net (code "101") (name "/XD11") (class "Default")
      (node (ref "U1") (pin "123") (pinfunction "GPIO68/XD11_123") (pintype "bidirectional"))
    )
    (net (code "102") (name "/XD12") (class "Default")
      (node (ref "U1") (pin "122") (pinfunction "GPIO67/XD12_122") (pintype "bidirectional"))
    )
    (net (code "103") (name "/XD13") (class "Default")
      (node (ref "U1") (pin "119") (pinfunction "GPIO66/XD13_119") (pintype "bidirectional"))
    )
    (net (code "104") (name "/XD14") (class "Default")
      (node (ref "U1") (pin "116") (pinfunction "GPIO65/XD14_116") (pintype "bidirectional"))
    )
    (net (code "105") (name "/XD15") (class "Default")
      (node (ref "U1") (pin "115") (pinfunction "GPIO64/XD15_115") (pintype "bidirectional"))
    )
    (net (code "107") (name "/XRDn") (class "Default")
      (node (ref "U1") (pin "149") (pinfunction "XRDn_149") (pintype "output"))
    )
    (net (code "108") (name "/XREADY") (class "Default")
      (node (ref "U1") (pin "142") (pinfunction "GPIO34/ECAP1/XREADY_142") (pintype "input"))
    )
    (net (code "109") (name "/XRSn") (class "Default")
      (node (ref "U1") (pin "80") (pinfunction "XRSn_80") (pintype "bidirectional"))
    )
    (net (code "110") (name "/XRWn") (class "Default")
      (node (ref "U1") (pin "148") (pinfunction "GPIO35/SCITXDA/XRWn_148") (pintype "output"))
    )
    (net (code "111") (name "/XWEn") (class "Default")
      (node (ref "U1") (pin "137") (pinfunction "GPIO38/XWE0n_137") (pintype "output"))
    )
    (net (code "112") (name "/XZCS0n") (class "Default")
      (node (ref "U1") (pin "145") (pinfunction "GPIO36/SCIRXDA/XZCS0n_145") (pintype "output"))
    )
    (net (code "113") (name "/XZCS6n") (class "Default")
      (node (ref "U1") (pin "141") (pinfunction "GPIO28/SCIRXDA/XZCS6n_141") (pintype "output"))
    )
    (net (code "114") (name "/XZCS7n") (class "Default")
      (node (ref "U1") (pin "150") (pinfunction "GPIO37/ECAP2/XZCS7n_150") (pintype "output"))
    )
    (net (code "115") (name "AGND") (class "Default")
      (node (ref "C44") (pin "2") (pinfunction "2_2") (pintype "passive"))
      (node (ref "C45") (pin "2") (pinfunction "2_2") (pintype "passive"))
      (node (ref "R40") (pin "1") (pinfunction "1_1") (pintype "passive"))
      (node (ref "U1") (pin "32") (pinfunction "VSS1AGND_32") (pintype "power_in"))
      (node (ref "U1") (pin "33") (pinfunction "VSSA2(AGND)_33") (pintype "power_in"))
      (node (ref "U1") (pin "35") (pinfunction "ADCINA7_35") (pintype "input"))
      (node (ref "U1") (pin "36") (pinfunction "ADCINA6_36") (pintype "input"))
      (node (ref "U1") (pin "37") (pinfunction "ADCINA5_37") (pintype "input"))
      (node (ref "U1") (pin "38") (pinfunction "ADCINA4_38") (pintype "input"))
      (node (ref "U1") (pin "43") (pinfunction "ADCLO_43") (pintype "input"))
      (node (ref "U1") (pin "44") (pinfunction "VSSAIO(AGND)_44") (pintype "power_in"))
      (node (ref "U1") (pin "46") (pinfunction "ADCINB0_46") (pintype "input"))
      (node (ref "U1") (pin "47") (pinfunction "ADCINB1_47") (pintype "input"))
      (node (ref "U1") (pin "48") (pinfunction "ADCINB2_48") (pintype "input"))
      (node (ref "U1") (pin "49") (pinfunction "ADCINB3_49") (pintype "input"))
      (node (ref "U1") (pin "50") (pinfunction "ADCINB4_50") (pintype "input"))
      (node (ref "U1") (pin "51") (pinfunction "ADCINB5_51") (pintype "input"))
      (node (ref "U1") (pin "52") (pinfunction "ADCINB6_52") (pintype "input"))
      (node (ref "U1") (pin "53") (pinfunction "ADCINB7_53") (pintype "input"))
      (node (ref "U1") (pin "58") (pinfunction "VSS2AGND_58") (pintype "power_in"))
    )
    (net (code "116") (name "GND") (class "Default")
      (node (ref "C41") (pin "1") (pinfunction "1_1") (pintype "passive"))
      (node (ref "C42") (pin "1") (pinfunction "1_1") (pintype "passive"))
      (node (ref "C43") (pin "1") (pinfunction "1_1") (pintype "passive"))
      (node (ref "JTAG_HEADER") (pin "10") (pinfunction "10_10") (pintype "passive"))
      (node (ref "JTAG_HEADER") (pin "12") (pinfunction "12_12") (pintype "passive"))
      (node (ref "JTAG_HEADER") (pin "4") (pinfunction "4_4") (pintype "passive"))
      (node (ref "JTAG_HEADER") (pin "6") (pinfunction "6_6") (pintype "passive"))
      (node (ref "JTAG_HEADER") (pin "8") (pinfunction "8_8") (pintype "passive"))
      (node (ref "OSC1") (pin "2") (pinfunction "GND_2") (pintype "power_in"))
      (node (ref "R31") (pin "2") (pinfunction "2_2") (pintype "passive"))
      (node (ref "R32") (pin "2") (pinfunction "2_2") (pintype "passive"))
      (node (ref "R33") (pin "2") (pinfunction "2_2") (pintype "passive"))
      (node (ref "R34") (pin "2") (pinfunction "2_2") (pintype "passive"))
      (node (ref "R41") (pin "2") (pinfunction "2_2") (pintype "passive"))
      (node (ref "U1") (pin "103") (pinfunction "VSS.10_103") (pintype "power_in"))
      (node (ref "U1") (pin "104") (pinfunction "X1_104") (pintype "input"))
      (node (ref "U1") (pin "106") (pinfunction "VSS.11_106") (pintype "power_in"))
      (node (ref "U1") (pin "108") (pinfunction "VSS.12_108") (pintype "power_in"))
      (node (ref "U1") (pin "118") (pinfunction "VSS.13_118") (pintype "power_in"))
      (node (ref "U1") (pin "120") (pinfunction "VSS.14_120") (pintype "power_in"))
      (node (ref "U1") (pin "125") (pinfunction "VSS.15_125") (pintype "power_in"))
      (node (ref "U1") (pin "14") (pinfunction "VSS.3_14") (pintype "power_in"))
      (node (ref "U1") (pin "140") (pinfunction "VSS.16_140") (pintype "power_in"))
      (node (ref "U1") (pin "144") (pinfunction "VSS.17_144") (pintype "power_in"))
      (node (ref "U1") (pin "147") (pinfunction "VSS.18_147") (pintype "power_in"))
      (node (ref "U1") (pin "155") (pinfunction "VSS.19_155") (pintype "power_in"))
      (node (ref "U1") (pin "160") (pinfunction "VSS.19_160") (pintype "power_in"))
      (node (ref "U1") (pin "166") (pinfunction "VSS.20_166") (pintype "power_in"))
      (node (ref "U1") (pin "171") (pinfunction "VSS.21_171") (pintype "power_in"))
      (node (ref "U1") (pin "22") (pinfunction "VSS.4_22") (pintype "power_in"))
      (node (ref "U1") (pin "3") (pinfunction "VSS.1_3") (pintype "power_in"))
      (node (ref "U1") (pin "30") (pinfunction "VSS.5_30") (pintype "power_in"))
      (node (ref "U1") (pin "60") (pinfunction "VSS.6_60") (pintype "power_in"))
      (node (ref "U1") (pin "70") (pinfunction "VSS.7_70") (pintype "power_in"))
      (node (ref "U1") (pin "8") (pinfunction "VSS.2_8") (pintype "power_in"))
      (node (ref "U1") (pin "83") (pinfunction "VSS.8_83") (pintype "power_in"))
      (node (ref "U1") (pin "92") (pinfunction "VSS.9_92") (pintype "power_in"))
    )
    (net (code "117") (name "Net-(DSP BOOT-Pad1)") (class "Default")
      (node (ref "DSP BOOT") (pin "1") (pinfunction "1_1") (pintype "passive"))
      (node (ref "R31") (pin "1") (pinfunction "1_1") (pintype "passive"))
    )
    (net (code "118") (name "Net-(DSP BOOT-Pad3)") (class "Default")
      (node (ref "DSP BOOT") (pin "3") (pinfunction "3_3") (pintype "passive"))
      (node (ref "R32") (pin "1") (pinfunction "1_1") (pintype "passive"))
    )
    (net (code "119") (name "Net-(DSP BOOT-Pad5)") (class "Default")
      (node (ref "DSP BOOT") (pin "5") (pinfunction "5_5") (pintype "passive"))
      (node (ref "R33") (pin "1") (pinfunction "1_1") (pintype "passive"))
    )
    (net (code "120") (name "Net-(DSP BOOT-Pad7)") (class "Default")
      (node (ref "DSP BOOT") (pin "7") (pinfunction "7_7") (pintype "passive"))
      (node (ref "R34") (pin "1") (pinfunction "1_1") (pintype "passive"))
    )
    (net (code "121") (name "Net-(JTAG_HEADER-Pad5)") (class "Default")
      (node (ref "JTAG_HEADER") (pin "5") (pinfunction "5_5") (pintype "passive"))
      (node (ref "R28") (pin "1") (pinfunction "1_1") (pintype "passive"))
    )
    (net (code "122") (name "Net-(OSC1-OUT)") (class "Default")
      (node (ref "OSC1") (pin "3") (pinfunction "OUT_3") (pintype "output"))
      (node (ref "R30") (pin "1") (pinfunction "1_1") (pintype "passive"))
    )
    (net (code "123") (name "Net-(U1-XCLKOUT)") (class "Default")
      (node (ref "R39") (pin "1") (pinfunction "1_1") (pintype "passive"))
      (node (ref "U1") (pin "138") (pinfunction "XCLKOUT_138") (pintype "output"))
    )
    (net (code "124") (name "unconnected-(U1-(NC)_TEST1-Pad81)") (class "Default")
      (node (ref "U1") (pin "81") (pinfunction "(NC)_TEST1_81") (pintype "input"))
    )
    (net (code "125") (name "unconnected-(U1-(NC)_TEST2-Pad82)") (class "Default")
      (node (ref "U1") (pin "82") (pinfunction "(NC)_TEST2_82") (pintype "input"))
    )
    (net (code "126") (name "unconnected-(U1-X2-Pad102)") (class "Default")
      (node (ref "U1") (pin "102") (pinfunction "X2_102") (pintype "input"))
    )
  )
)
